# 4_LEDDRIVERS.net
KiCad netlist of a schematic drawn in Altium Designer
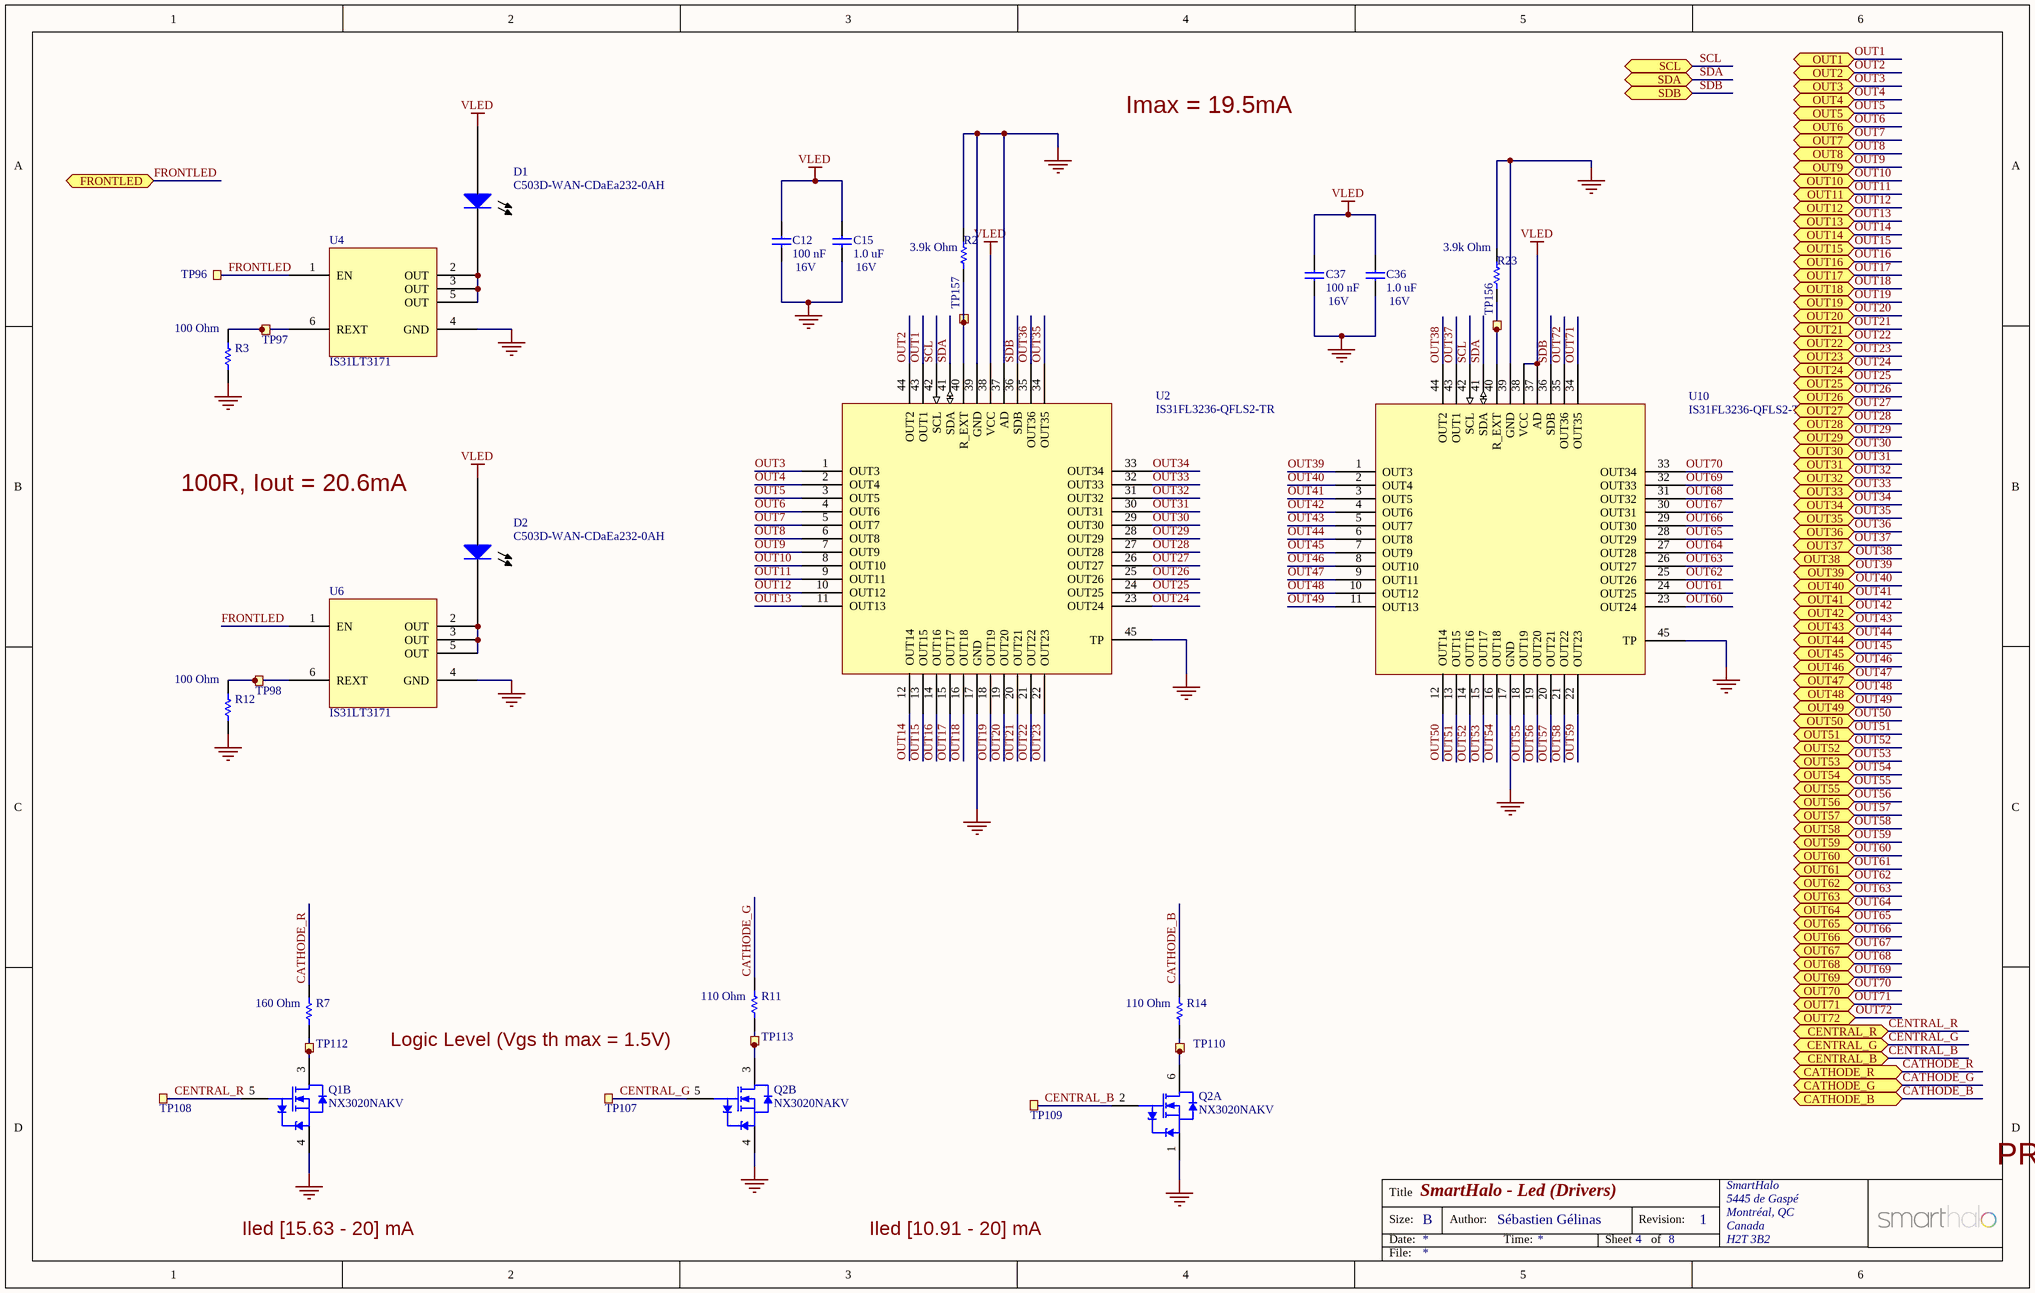
[diagram p0: 4_LEDDRIVERS.SchDoc]

(export (version "E")
  (design (tool "Eeschema 10.0.6"))
  (components
    (comp (ref "C12")
      (value "100 nF")
      (footprint "Varitron_CAP0402")
      (description "100 nF 16V X7R 10% 0402 (1005 Metric)  SMD")
      (fields
        (field (name "TOLERANCE") "10%")
        (field (name "VOLTAGE RATING") "16V")
        (field (name "MANUFACTURER") "Samsung")
      )
      (libsource (lib "SmartHalo") (part "Varitron_CAP0402"))
    )
    (comp (ref "C15")
      (value "1.0 uF")
      (footprint "Varitron_CAP0603")
      (description "1.0 uF 16V X7R 10% 0603 (1608 Metric)  SMD")
      (fields
        (field (name "TOLERANCE") "10%")
        (field (name "VOLTAGE RATING") "16V")
        (field (name "MANUFACTURER") "Samsung")
      )
      (libsource (lib "SmartHalo") (part "Varitron_CAP0603"))
    )
    (comp (ref "C36")
      (value "1.0 uF")
      (footprint "Varitron_CAP0603")
      (description "1.0 uF 16V X7R 10% 0603 (1608 Metric)  SMD")
      (fields
        (field (name "TOLERANCE") "10%")
        (field (name "VOLTAGE RATING") "16V")
        (field (name "MANUFACTURER") "Samsung")
      )
      (libsource (lib "SmartHalo") (part "Varitron_CAP0603"))
    )
    (comp (ref "C37")
      (value "100 nF")
      (footprint "Varitron_CAP0402")
      (description "100 nF 16V X7R 10% 0402 (1005 Metric)  SMD")
      (fields
        (field (name "TOLERANCE") "10%")
        (field (name "VOLTAGE RATING") "16V")
        (field (name "MANUFACTURER") "Samsung")
      )
      (libsource (lib "SmartHalo") (part "Varitron_CAP0402"))
    )
    (comp (ref "D1")
      (value "C503D-WAN-CDaEa232-0AH")
      (footprint "FRONTLED_PADS")
      (description "Cree 5mm Round LED C503D-WAN-CDaEa232-0AH")
      (fields (field (name "MANUFACTURER") "Cree") (field (name "SMARTHALO PART NUMBER") "630016-01"))
      (libsource (lib "SmartHalo") (part "C503D-WAN-CDaEa232-0AH"))
    )
    (comp (ref "D2")
      (value "C503D-WAN-CDaEa232-0AH")
      (footprint "FRONTLED_PADS")
      (description "Cree 5mm Round LED C503D-WAN-CDaEa232-0AH")
      (fields (field (name "MANUFACTURER") "Cree") (field (name "SMARTHALO PART NUMBER") "630016-01"))
      (libsource (lib "SmartHalo") (part "C503D-WAN-CDaEa232-0AH"))
    )
    (comp (ref "Q1")
      (value "NX3020NAKV")
      (footprint "SOT666")
      (description "30 V, 200 mA dual N-channel Trench MOSFET")
      (fields
        (field (name "MANUFACTURER") "NXP Semiconductors")
        (field (name "SMARTHALO PART NUMBER") "630030-01")
      )
      (libsource (lib "SmartHalo") (part "NX3020NAKV"))
    )
    (comp (ref "Q2")
      (value "NX3020NAKV")
      (footprint "SOT666")
      (description "30 V, 200 mA dual N-channel Trench MOSFET")
      (fields
        (field (name "MANUFACTURER") "NXP Semiconductors")
        (field (name "SMARTHALO PART NUMBER") "630030-01")
      )
      (libsource (lib "SmartHalo") (part "NX3020NAKV"))
    )
    (comp (ref "R2")
      (value "3.9k Ohm")
      (footprint "Varitron_RES0402")
      (description "3k9 0.063W 5%  0402 (1005 Metric)  SMD")
      (fields (field (name "TOLERANCE") "5%") (field (name "POWER") "0.063W"))
      (libsource (lib "SmartHalo") (part "Varitron_RES0402"))
    )
    (comp (ref "R3")
      (value "100 Ohm")
      (footprint "Varitron_RES0402")
      (description "100R 0.1W 5%  0402 (1005 Metric)  SMD")
      (fields (field (name "TOLERANCE") "5%") (field (name "POWER") "0.1W"))
      (libsource (lib "SmartHalo") (part "Varitron_RES0402"))
    )
    (comp (ref "R7")
      (value "160 Ohm")
      (footprint "Varitron_RES0402")
      (description "160R 0.1W 5%  0402 (1005 Metric)  SMD")
      (fields (field (name "TOLERANCE") "5%") (field (name "POWER") "0.1W"))
      (libsource (lib "SmartHalo") (part "Varitron_RES0402"))
    )
    (comp (ref "R11")
      (value "110 Ohm")
      (footprint "Varitron_RES0402")
      (description "110R 0.1W 5%  0402 (1005 Metric)  SMD")
      (fields (field (name "TOLERANCE") "5%") (field (name "POWER") "0.1W"))
      (libsource (lib "SmartHalo") (part "Varitron_RES0402"))
    )
    (comp (ref "R12")
      (value "100 Ohm")
      (footprint "Varitron_RES0402")
      (description "100R 0.1W 5%  0402 (1005 Metric)  SMD")
      (fields (field (name "TOLERANCE") "5%") (field (name "POWER") "0.1W"))
      (libsource (lib "SmartHalo") (part "Varitron_RES0402"))
    )
    (comp (ref "R14")
      (value "110 Ohm")
      (footprint "Varitron_RES0402")
      (description "110R 0.1W 5%  0402 (1005 Metric)  SMD")
      (fields (field (name "TOLERANCE") "5%") (field (name "POWER") "0.1W"))
      (libsource (lib "SmartHalo") (part "Varitron_RES0402"))
    )
    (comp (ref "R23")
      (value "3.9k Ohm")
      (footprint "Varitron_RES0402")
      (description "3k9 0.063W 5%  0402 (1005 Metric)  SMD")
      (fields (field (name "TOLERANCE") "5%") (field (name "POWER") "0.063W"))
      (libsource (lib "SmartHalo") (part "Varitron_RES0402"))
    )
    (comp (ref "TP96")
      (value "TP96")
      (footprint "TESTPAD-TH-35mils")
      (description "Testpoint, through hole, 35 mils")
      (libsource (lib "") (part "TESTPAD_TH_35mils_1"))
    )
    (comp (ref "TP97")
      (value "TP97")
      (footprint "TESTPAD-TH-35mils")
      (description "Testpoint, through hole, 35 mils")
      (libsource (lib "") (part "TESTPAD_TH_35mils_2"))
    )
    (comp (ref "TP98")
      (value "TP98")
      (footprint "TESTPAD-TH-35mils")
      (description "Testpoint, through hole, 35 mils")
      (libsource (lib "") (part "TESTPAD_TH_35mils_2"))
    )
    (comp (ref "TP107")
      (value "TP107")
      (footprint "TESTPAD-TH-35mils")
      (description "Testpoint, through hole, 35 mils")
      (libsource (lib "") (part "TESTPAD_TH_35mils_1"))
    )
    (comp (ref "TP108")
      (value "TP108")
      (footprint "TESTPAD-TH-35mils")
      (description "Testpoint, through hole, 35 mils")
      (libsource (lib "") (part "TESTPAD_TH_35mils_1"))
    )
    (comp (ref "TP109")
      (value "TP109")
      (footprint "TESTPAD-TH-35mils")
      (description "Testpoint, through hole, 35 mils")
      (libsource (lib "") (part "TESTPAD_TH_35mils_1"))
    )
    (comp (ref "TP110")
      (value "TP110")
      (footprint "TESTPAD-TH-35mils")
      (description "Testpoint, through hole, 35 mils")
      (libsource (lib "SmartHalo") (part "TESTPAD_TH_35mils"))
    )
    (comp (ref "TP112")
      (value "TP112")
      (footprint "TESTPAD-TH-35mils")
      (description "Testpoint, through hole, 35 mils")
      (libsource (lib "SmartHalo") (part "TESTPAD_TH_35mils"))
    )
    (comp (ref "TP113")
      (value "TP113")
      (footprint "TESTPAD-TH-35mils")
      (description "Testpoint, through hole, 35 mils")
      (libsource (lib "SmartHalo") (part "TESTPAD_TH_35mils"))
    )
    (comp (ref "TP156")
      (value "TP156")
      (footprint "TESTPAD-TH-35mils")
      (description "Testpoint, through hole, 35 mils")
      (libsource (lib "SmartHalo") (part "TESTPAD_TH_35mils"))
    )
    (comp (ref "TP157")
      (value "TP157")
      (footprint "TESTPAD-TH-35mils")
      (description "Testpoint, through hole, 35 mils")
      (libsource (lib "SmartHalo") (part "TESTPAD_TH_35mils"))
    )
    (comp (ref "U2")
      (value "IS31FL3236-QFLS2-TR")
      (footprint "QFN-44")
      (description "IC 36 CHANNELS LED DRIVER")
      (fields (field (name "MANUFACTURER") "ISSI") (field (name "SMARTHALO PART NUMBER") "630052-01"))
      (libsource (lib "SmartHalo") (part "IS31FL3236-QFLS2-TR"))
    )
    (comp (ref "U4")
      (value "IS31LT3171")
      (footprint "SOT23-6")
      (description "10-TO-150MA CONSTANT-CURRENT LED DRIVER")
      (fields (field (name "MANUFACTURER") "ISSI") (field (name "SMARTHALO PART NUMBER") "630054-01"))
      (libsource (lib "SmartHalo") (part "IS31LT3171"))
    )
    (comp (ref "U6")
      (value "IS31LT3171")
      (footprint "SOT23-6")
      (description "10-TO-150MA CONSTANT-CURRENT LED DRIVER")
      (fields (field (name "MANUFACTURER") "ISSI") (field (name "SMARTHALO PART NUMBER") "630054-01"))
      (libsource (lib "SmartHalo") (part "IS31LT3171"))
    )
    (comp (ref "U10")
      (value "IS31FL3236-QFLS2-TR")
      (footprint "QFN-44")
      (description "IC 36 CHANNELS LED DRIVER")
      (fields (field (name "MANUFACTURER") "ISSI") (field (name "SMARTHALO PART NUMBER") "630052-01"))
      (libsource (lib "SmartHalo") (part "IS31FL3236-QFLS2-TR"))
    )
  )
  (nets
    (net (code "1") (name "/CATHODE_B") (class "Default")
      (node (ref "R14") (pin "2") (pinfunction "2_2") (pintype "passive"))
    )
    (net (code "2") (name "/CATHODE_G") (class "Default")
      (node (ref "R11") (pin "2") (pinfunction "2_2") (pintype "passive"))
    )
    (net (code "3") (name "/CATHODE_R") (class "Default")
      (node (ref "R7") (pin "2") (pinfunction "2_2") (pintype "passive"))
    )
    (net (code "4") (name "/CENTRAL_B") (class "Default")
      (node (ref "Q2") (pin "2") (pinfunction "G1_2") (pintype "passive"))
      (node (ref "TP109") (pin "1") (pinfunction "1_1") (pintype "passive"))
    )
    (net (code "5") (name "/CENTRAL_G") (class "Default")
      (node (ref "Q2") (pin "5") (pinfunction "G2_5") (pintype "passive"))
      (node (ref "TP107") (pin "1") (pinfunction "1_1") (pintype "passive"))
    )
    (net (code "6") (name "/CENTRAL_R") (class "Default")
      (node (ref "Q1") (pin "5") (pinfunction "G2_5") (pintype "passive"))
      (node (ref "TP108") (pin "1") (pinfunction "1_1") (pintype "passive"))
    )
    (net (code "7") (name "/FRONTLED") (class "Default")
      (node (ref "TP96") (pin "1") (pinfunction "1_1") (pintype "passive"))
      (node (ref "U4") (pin "1") (pinfunction "EN_1") (pintype "passive"))
      (node (ref "U6") (pin "1") (pinfunction "EN_1") (pintype "passive"))
    )
    (net (code "8") (name "/OUT1") (class "Default")
      (node (ref "U2") (pin "43") (pinfunction "OUT1_43") (pintype "passive"))
    )
    (net (code "9") (name "/OUT2") (class "Default")
      (node (ref "U2") (pin "44") (pinfunction "OUT2_44") (pintype "passive"))
    )
    (net (code "10") (name "/OUT3") (class "Default")
      (node (ref "U2") (pin "1") (pinfunction "OUT3_1") (pintype "passive"))
    )
    (net (code "11") (name "/OUT4") (class "Default")
      (node (ref "U2") (pin "2") (pinfunction "OUT4_2") (pintype "passive"))
    )
    (net (code "12") (name "/OUT5") (class "Default")
      (node (ref "U2") (pin "3") (pinfunction "OUT5_3") (pintype "passive"))
    )
    (net (code "13") (name "/OUT6") (class "Default")
      (node (ref "U2") (pin "4") (pinfunction "OUT6_4") (pintype "passive"))
    )
    (net (code "14") (name "/OUT7") (class "Default")
      (node (ref "U2") (pin "5") (pinfunction "OUT7_5") (pintype "passive"))
    )
    (net (code "15") (name "/OUT8") (class "Default")
      (node (ref "U2") (pin "6") (pinfunction "OUT8_6") (pintype "passive"))
    )
    (net (code "16") (name "/OUT9") (class "Default")
      (node (ref "U2") (pin "7") (pinfunction "OUT9_7") (pintype "passive"))
    )
    (net (code "17") (name "/OUT10") (class "Default")
      (node (ref "U2") (pin "8") (pinfunction "OUT10_8") (pintype "passive"))
    )
    (net (code "18") (name "/OUT11") (class "Default")
      (node (ref "U2") (pin "9") (pinfunction "OUT11_9") (pintype "passive"))
    )
    (net (code "19") (name "/OUT12") (class "Default")
      (node (ref "U2") (pin "10") (pinfunction "OUT12_10") (pintype "passive"))
    )
    (net (code "20") (name "/OUT13") (class "Default")
      (node (ref "U2") (pin "11") (pinfunction "OUT13_11") (pintype "passive"))
    )
    (net (code "21") (name "/OUT14") (class "Default")
      (node (ref "U2") (pin "12") (pinfunction "OUT14_12") (pintype "passive"))
    )
    (net (code "22") (name "/OUT15") (class "Default")
      (node (ref "U2") (pin "13") (pinfunction "OUT15_13") (pintype "passive"))
    )
    (net (code "23") (name "/OUT16") (class "Default")
      (node (ref "U2") (pin "14") (pinfunction "OUT16_14") (pintype "passive"))
    )
    (net (code "24") (name "/OUT17") (class "Default")
      (node (ref "U2") (pin "15") (pinfunction "OUT17_15") (pintype "passive"))
    )
    (net (code "25") (name "/OUT18") (class "Default")
      (node (ref "U2") (pin "16") (pinfunction "OUT18_16") (pintype "passive"))
    )
    (net (code "26") (name "/OUT19") (class "Default")
      (node (ref "U2") (pin "18") (pinfunction "OUT19_18") (pintype "passive"))
    )
    (net (code "27") (name "/OUT20") (class "Default")
      (node (ref "U2") (pin "19") (pinfunction "OUT20_19") (pintype "passive"))
    )
    (net (code "28") (name "/OUT21") (class "Default")
      (node (ref "U2") (pin "20") (pinfunction "OUT21_20") (pintype "passive"))
    )
    (net (code "29") (name "/OUT22") (class "Default")
      (node (ref "U2") (pin "21") (pinfunction "OUT22_21") (pintype "passive"))
    )
    (net (code "30") (name "/OUT23") (class "Default")
      (node (ref "U2") (pin "22") (pinfunction "OUT23_22") (pintype "passive"))
    )
    (net (code "31") (name "/OUT24") (class "Default")
      (node (ref "U2") (pin "23") (pinfunction "OUT24_23") (pintype "passive"))
    )
    (net (code "32") (name "/OUT25") (class "Default")
      (node (ref "U2") (pin "24") (pinfunction "OUT25_24") (pintype "passive"))
    )
    (net (code "33") (name "/OUT26") (class "Default")
      (node (ref "U2") (pin "25") (pinfunction "OUT26_25") (pintype "passive"))
    )
    (net (code "34") (name "/OUT27") (class "Default")
      (node (ref "U2") (pin "26") (pinfunction "OUT27_26") (pintype "passive"))
    )
    (net (code "35") (name "/OUT28") (class "Default")
      (node (ref "U2") (pin "27") (pinfunction "OUT28_27") (pintype "passive"))
    )
    (net (code "36") (name "/OUT29") (class "Default")
      (node (ref "U2") (pin "28") (pinfunction "OUT29_28") (pintype "passive"))
    )
    (net (code "37") (name "/OUT30") (class "Default")
      (node (ref "U2") (pin "29") (pinfunction "OUT30_29") (pintype "passive"))
    )
    (net (code "38") (name "/OUT31") (class "Default")
      (node (ref "U2") (pin "30") (pinfunction "OUT31_30") (pintype "passive"))
    )
    (net (code "39") (name "/OUT32") (class "Default")
      (node (ref "U2") (pin "31") (pinfunction "OUT32_31") (pintype "passive"))
    )
    (net (code "40") (name "/OUT33") (class "Default")
      (node (ref "U2") (pin "32") (pinfunction "OUT33_32") (pintype "passive"))
    )
    (net (code "41") (name "/OUT34") (class "Default")
      (node (ref "U2") (pin "33") (pinfunction "OUT34_33") (pintype "passive"))
    )
    (net (code "42") (name "/OUT35") (class "Default")
      (node (ref "U2") (pin "34") (pinfunction "OUT35_34") (pintype "passive"))
    )
    (net (code "43") (name "/OUT36") (class "Default")
      (node (ref "U2") (pin "35") (pinfunction "OUT36_35") (pintype "passive"))
    )
    (net (code "44") (name "/OUT37") (class "Default")
      (node (ref "U10") (pin "43") (pinfunction "OUT1_43") (pintype "passive"))
    )
    (net (code "45") (name "/OUT38") (class "Default")
      (node (ref "U10") (pin "44") (pinfunction "OUT2_44") (pintype "passive"))
    )
    (net (code "46") (name "/OUT39") (class "Default")
      (node (ref "U10") (pin "1") (pinfunction "OUT3_1") (pintype "passive"))
    )
    (net (code "47") (name "/OUT40") (class "Default")
      (node (ref "U10") (pin "2") (pinfunction "OUT4_2") (pintype "passive"))
    )
    (net (code "48") (name "/OUT41") (class "Default")
      (node (ref "U10") (pin "3") (pinfunction "OUT5_3") (pintype "passive"))
    )
    (net (code "49") (name "/OUT42") (class "Default")
      (node (ref "U10") (pin "4") (pinfunction "OUT6_4") (pintype "passive"))
    )
    (net (code "50") (name "/OUT43") (class "Default")
      (node (ref "U10") (pin "5") (pinfunction "OUT7_5") (pintype "passive"))
    )
    (net (code "51") (name "/OUT44") (class "Default")
      (node (ref "U10") (pin "6") (pinfunction "OUT8_6") (pintype "passive"))
    )
    (net (code "52") (name "/OUT45") (class "Default")
      (node (ref "U10") (pin "7") (pinfunction "OUT9_7") (pintype "passive"))
    )
    (net (code "53") (name "/OUT46") (class "Default")
      (node (ref "U10") (pin "8") (pinfunction "OUT10_8") (pintype "passive"))
    )
    (net (code "54") (name "/OUT47") (class "Default")
      (node (ref "U10") (pin "9") (pinfunction "OUT11_9") (pintype "passive"))
    )
    (net (code "55") (name "/OUT48") (class "Default")
      (node (ref "U10") (pin "10") (pinfunction "OUT12_10") (pintype "passive"))
    )
    (net (code "56") (name "/OUT49") (class "Default")
      (node (ref "U10") (pin "11") (pinfunction "OUT13_11") (pintype "passive"))
    )
    (net (code "57") (name "/OUT50") (class "Default")
      (node (ref "U10") (pin "12") (pinfunction "OUT14_12") (pintype "passive"))
    )
    (net (code "58") (name "/OUT51") (class "Default")
      (node (ref "U10") (pin "13") (pinfunction "OUT15_13") (pintype "passive"))
    )
    (net (code "59") (name "/OUT52") (class "Default")
      (node (ref "U10") (pin "14") (pinfunction "OUT16_14") (pintype "passive"))
    )
    (net (code "60") (name "/OUT53") (class "Default")
      (node (ref "U10") (pin "15") (pinfunction "OUT17_15") (pintype "passive"))
    )
    (net (code "61") (name "/OUT54") (class "Default")
      (node (ref "U10") (pin "16") (pinfunction "OUT18_16") (pintype "passive"))
    )
    (net (code "62") (name "/OUT55") (class "Default")
      (node (ref "U10") (pin "18") (pinfunction "OUT19_18") (pintype "passive"))
    )
    (net (code "63") (name "/OUT56") (class "Default")
      (node (ref "U10") (pin "19") (pinfunction "OUT20_19") (pintype "passive"))
    )
    (net (code "64") (name "/OUT57") (class "Default")
      (node (ref "U10") (pin "20") (pinfunction "OUT21_20") (pintype "passive"))
    )
    (net (code "65") (name "/OUT58") (class "Default")
      (node (ref "U10") (pin "21") (pinfunction "OUT22_21") (pintype "passive"))
    )
    (net (code "66") (name "/OUT59") (class "Default")
      (node (ref "U10") (pin "22") (pinfunction "OUT23_22") (pintype "passive"))
    )
    (net (code "67") (name "/OUT60") (class "Default")
      (node (ref "U10") (pin "23") (pinfunction "OUT24_23") (pintype "passive"))
    )
    (net (code "68") (name "/OUT61") (class "Default")
      (node (ref "U10") (pin "24") (pinfunction "OUT25_24") (pintype "passive"))
    )
    (net (code "69") (name "/OUT62") (class "Default")
      (node (ref "U10") (pin "25") (pinfunction "OUT26_25") (pintype "passive"))
    )
    (net (code "70") (name "/OUT63") (class "Default")
      (node (ref "U10") (pin "26") (pinfunction "OUT27_26") (pintype "passive"))
    )
    (net (code "71") (name "/OUT64") (class "Default")
      (node (ref "U10") (pin "27") (pinfunction "OUT28_27") (pintype "passive"))
    )
    (net (code "72") (name "/OUT65") (class "Default")
      (node (ref "U10") (pin "28") (pinfunction "OUT29_28") (pintype "passive"))
    )
    (net (code "73") (name "/OUT66") (class "Default")
      (node (ref "U10") (pin "29") (pinfunction "OUT30_29") (pintype "passive"))
    )
    (net (code "74") (name "/OUT67") (class "Default")
      (node (ref "U10") (pin "30") (pinfunction "OUT31_30") (pintype "passive"))
    )
    (net (code "75") (name "/OUT68") (class "Default")
      (node (ref "U10") (pin "31") (pinfunction "OUT32_31") (pintype "passive"))
    )
    (net (code "76") (name "/OUT69") (class "Default")
      (node (ref "U10") (pin "32") (pinfunction "OUT33_32") (pintype "passive"))
    )
    (net (code "77") (name "/OUT70") (class "Default")
      (node (ref "U10") (pin "33") (pinfunction "OUT34_33") (pintype "passive"))
    )
    (net (code "78") (name "/OUT71") (class "Default")
      (node (ref "U10") (pin "34") (pinfunction "OUT35_34") (pintype "passive"))
    )
    (net (code "79") (name "/OUT72") (class "Default")
      (node (ref "U10") (pin "35") (pinfunction "OUT36_35") (pintype "passive"))
    )
    (net (code "80") (name "/SCL") (class "Default")
      (node (ref "U10") (pin "42") (pinfunction "SCL_42") (pintype "input"))
      (node (ref "U2") (pin "42") (pinfunction "SCL_42") (pintype "input"))
    )
    (net (code "81") (name "/SDA") (class "Default")
      (node (ref "U10") (pin "41") (pinfunction "SDA_41") (pintype "bidirectional"))
      (node (ref "U2") (pin "41") (pinfunction "SDA_41") (pintype "bidirectional"))
    )
    (net (code "82") (name "/SDB") (class "Default")
      (node (ref "U10") (pin "36") (pinfunction "SDB_36") (pintype "passive"))
      (node (ref "U2") (pin "36") (pinfunction "SDB_36") (pintype "passive"))
    )
    (net (code "83") (name "GND") (class "Default")
      (node (ref "C12") (pin "2") (pinfunction "2_2") (pintype "passive"))
      (node (ref "C15") (pin "2") (pinfunction "2_2") (pintype "passive"))
      (node (ref "C36") (pin "2") (pinfunction "2_2") (pintype "passive"))
      (node (ref "C37") (pin "2") (pinfunction "2_2") (pintype "passive"))
      (node (ref "Q1") (pin "4") (pinfunction "S2_4") (pintype "passive"))
      (node (ref "Q2") (pin "1") (pinfunction "S1_1") (pintype "passive"))
      (node (ref "Q2") (pin "4") (pinfunction "S2_4") (pintype "passive"))
      (node (ref "R12") (pin "1") (pinfunction "1_1") (pintype "passive"))
      (node (ref "R2") (pin "2") (pinfunction "2_2") (pintype "passive"))
      (node (ref "R23") (pin "2") (pinfunction "2_2") (pintype "passive"))
      (node (ref "R3") (pin "1") (pinfunction "1_1") (pintype "passive"))
      (node (ref "U10") (pin "17") (pinfunction "GND_17") (pintype "power_in"))
      (node (ref "U10") (pin "39") (pinfunction "GND_39") (pintype "power_in"))
      (node (ref "U10") (pin "45") (pinfunction "TP_45") (pintype "power_in"))
      (node (ref "U2") (pin "17") (pinfunction "GND_17") (pintype "power_in"))
      (node (ref "U2") (pin "37") (pinfunction "AD_37") (pintype "passive"))
      (node (ref "U2") (pin "39") (pinfunction "GND_39") (pintype "power_in"))
      (node (ref "U2") (pin "45") (pinfunction "TP_45") (pintype "power_in"))
      (node (ref "U4") (pin "4") (pinfunction "GND_4") (pintype "passive"))
      (node (ref "U6") (pin "4") (pinfunction "GND_4") (pintype "passive"))
    )
    (net (code "84") (name "Net-(D1-Cathode)") (class "Default")
      (node (ref "D1") (pin "2") (pinfunction "Cathode_2") (pintype "passive"))
      (node (ref "U4") (pin "2") (pinfunction "OUT_2") (pintype "passive"))
      (node (ref "U4") (pin "3") (pinfunction "OUT_3") (pintype "passive"))
      (node (ref "U4") (pin "5") (pinfunction "OUT_5") (pintype "passive"))
    )
    (net (code "85") (name "Net-(D2-Cathode)") (class "Default")
      (node (ref "D2") (pin "2") (pinfunction "Cathode_2") (pintype "passive"))
      (node (ref "U6") (pin "2") (pinfunction "OUT_2") (pintype "passive"))
      (node (ref "U6") (pin "3") (pinfunction "OUT_3") (pintype "passive"))
      (node (ref "U6") (pin "5") (pinfunction "OUT_5") (pintype "passive"))
    )
    (net (code "86") (name "Net-(Q1B-D2)") (class "Default")
      (node (ref "Q1") (pin "3") (pinfunction "D2_3") (pintype "passive"))
      (node (ref "R7") (pin "1") (pinfunction "1_1") (pintype "passive"))
      (node (ref "TP112") (pin "1") (pinfunction "1_1") (pintype "passive"))
    )
    (net (code "87") (name "Net-(Q2A-D1)") (class "Default")
      (node (ref "Q2") (pin "6") (pinfunction "D1_6") (pintype "passive"))
      (node (ref "R14") (pin "1") (pinfunction "1_1") (pintype "passive"))
      (node (ref "TP110") (pin "1") (pinfunction "1_1") (pintype "passive"))
    )
    (net (code "88") (name "Net-(Q2B-D2)") (class "Default")
      (node (ref "Q2") (pin "3") (pinfunction "D2_3") (pintype "passive"))
      (node (ref "R11") (pin "1") (pinfunction "1_1") (pintype "passive"))
      (node (ref "TP113") (pin "1") (pinfunction "1_1") (pintype "passive"))
    )
    (net (code "89") (name "Net-(U2-R_EXT)") (class "Default")
      (node (ref "R2") (pin "1") (pinfunction "1_1") (pintype "passive"))
      (node (ref "TP157") (pin "1") (pinfunction "1_1") (pintype "passive"))
      (node (ref "U2") (pin "40") (pinfunction "R_EXT_40") (pintype "passive"))
    )
    (net (code "90") (name "Net-(U4-REXT)") (class "Default")
      (node (ref "R3") (pin "2") (pinfunction "2_2") (pintype "passive"))
      (node (ref "TP97") (pin "1") (pinfunction "1_1") (pintype "passive"))
      (node (ref "U4") (pin "6") (pinfunction "REXT_6") (pintype "passive"))
    )
    (net (code "91") (name "Net-(U6-REXT)") (class "Default")
      (node (ref "R12") (pin "2") (pinfunction "2_2") (pintype "passive"))
      (node (ref "TP98") (pin "1") (pinfunction "1_1") (pintype "passive"))
      (node (ref "U6") (pin "6") (pinfunction "REXT_6") (pintype "passive"))
    )
    (net (code "92") (name "Net-(U10-R_EXT)") (class "Default")
      (node (ref "R23") (pin "1") (pinfunction "1_1") (pintype "passive"))
      (node (ref "TP156") (pin "1") (pinfunction "1_1") (pintype "passive"))
      (node (ref "U10") (pin "40") (pinfunction "R_EXT_40") (pintype "passive"))
    )
    (net (code "93") (name "VLED") (class "Default")
      (node (ref "C12") (pin "1") (pinfunction "1_1") (pintype "passive"))
      (node (ref "C15") (pin "1") (pinfunction "1_1") (pintype "passive"))
      (node (ref "C36") (pin "1") (pinfunction "1_1") (pintype "passive"))
      (node (ref "C37") (pin "1") (pinfunction "1_1") (pintype "passive"))
      (node (ref "D1") (pin "1") (pinfunction "Anode_1") (pintype "passive"))
      (node (ref "D2") (pin "1") (pinfunction "Anode_1") (pintype "passive"))
      (node (ref "U10") (pin "37") (pinfunction "AD_37") (pintype "passive"))
      (node (ref "U10") (pin "38") (pinfunction "VCC_38") (pintype "power_in"))
      (node (ref "U2") (pin "38") (pinfunction "VCC_38") (pintype "power_in"))
    )
  )
)
